# LPCB224_-_TEENSY.net
KiCad netlist of a schematic drawn in Altium Designer
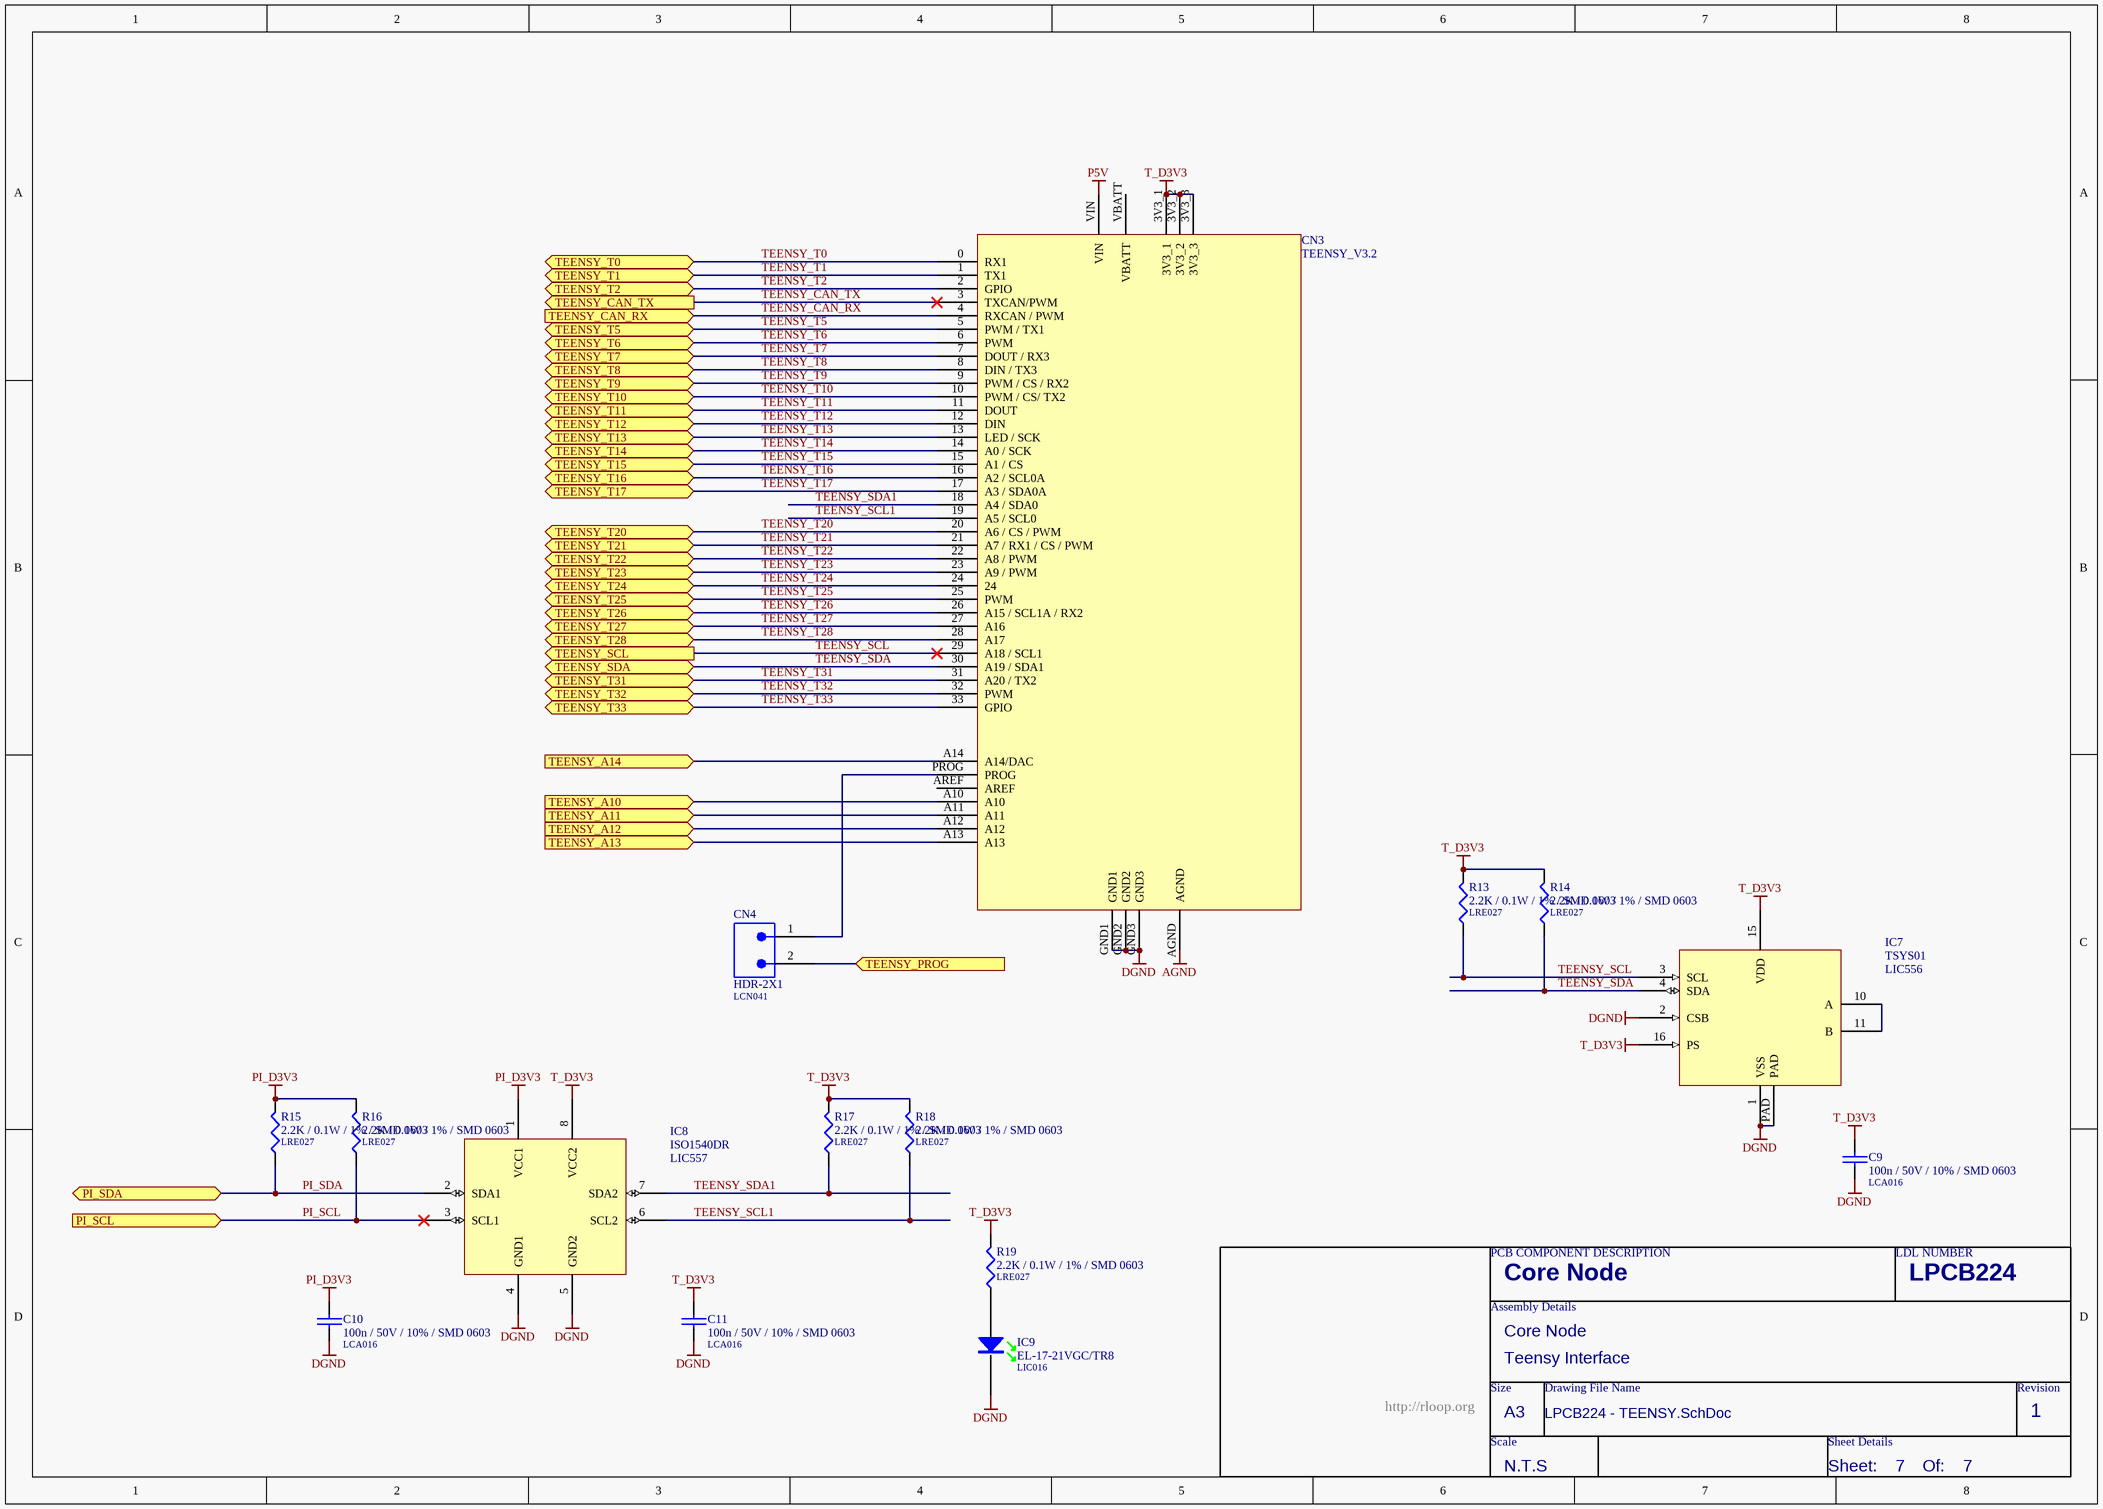
[diagram p0: LPCB224 - TEENSY.SchDoc]

(export (version "E")
  (design (tool "Eeschema 10.0.6"))
  (components
    (comp (ref "C9")
      (value "100n / 50V / 10% / SMD 0603")
      (footprint "LFP011__CC1608-0603-IPC7351_B")
      (description "Capacitor, Ceramic Chip, 100nF (0.1uF), 50V, 5%, SMD 0603 [LCA016]")
      (fields (field (name "LDL_NUMBER") "LCA016"))
      (libsource (lib "LDL_Capacitors") (part "100n / 50V / 10% / SMD 0603"))
    )
    (comp (ref "C10")
      (value "100n / 50V / 10% / SMD 0603")
      (footprint "LFP011__CC1608-0603-IPC7351_B")
      (description "Capacitor, Ceramic Chip, 100nF (0.1uF), 50V, 5%, SMD 0603 [LCA016]")
      (fields (field (name "LDL_NUMBER") "LCA016"))
      (libsource (lib "LDL_Capacitors") (part "100n / 50V / 10% / SMD 0603"))
    )
    (comp (ref "C11")
      (value "100n / 50V / 10% / SMD 0603")
      (footprint "LFP011__CC1608-0603-IPC7351_B")
      (description "Capacitor, Ceramic Chip, 100nF (0.1uF), 50V, 5%, SMD 0603 [LCA016]")
      (fields (field (name "LDL_NUMBER") "LCA016"))
      (libsource (lib "LDL_Capacitors") (part "100n / 50V / 10% / SMD 0603"))
    )
    (comp (ref "CN3")
      (value "TEENSY_V3.2")
      (footprint "TEENSY_V3.2")
      (libsource (lib "LDL_Semiconductors") (part "TEENSY_V3.2"))
    )
    (comp (ref "CN4")
      (value "HDR-2X1")
      (footprint "HDR-2X1")
      (description "Header, 2.54mm (0.1in), 2 Pins x 1 Row (40 Per Row In Strip)")
      (fields (field (name "LDL_NUMBER") "LCN041"))
      (libsource (lib "LDL_Connectors") (part "HDR-2X1"))
    )
    (comp (ref "IC7")
      (value "TSYS01")
      (footprint "LFP135__QFN65P400X400X80_HS-17M")
      (description "IC, Digital Temp Sensor, SMD QFN16 [LIC556]")
      (fields (field (name "LDL_NUMBER") "LIC556"))
      (libsource (lib "LDL_Semiconductors") (part "TSYS01"))
    )
    (comp (ref "IC8")
      (value "ISO1540DR")
      (footprint "LFP097__SOIC150-8")
      (description "IC, Digital Isolator for I2C, SMD SOIC8")
      (fields (field (name "LDL_NUMBER") "LIC557"))
      (libsource (lib "LDL_Semiconductors") (part "ISO1540DR"))
    )
    (comp (ref "IC9")
      (value "EL-17-21VGC/TR8")
      (footprint "CR2012-0805-LED")
      (description "LED, SMD, 0805 Green [LIC016]")
      (fields (field (name "LDL_NUMBER") "LIC016"))
      (libsource (lib "LDL_Semiconductors") (part "EL-17-21VGC/TR8"))
    )
    (comp (ref "R13")
      (value "2.2K / 0.1W / 1% / SMD 0603")
      (footprint "LFP020__CR1608-0603-IPC7351_B")
      (description "Resistor, Ceramic Chip, 2.2K, 0.1W, 1%, SMD 0603 [LRE027]")
      (fields (field (name "LDL_NUMBER") "LRE027"))
      (libsource (lib "LDL_Resistors") (part "2.2K / 0.1W / 1% / SMD 0603"))
    )
    (comp (ref "R14")
      (value "2.2K / 0.1W / 1% / SMD 0603")
      (footprint "LFP020__CR1608-0603-IPC7351_B")
      (description "Resistor, Ceramic Chip, 2.2K, 0.1W, 1%, SMD 0603 [LRE027]")
      (fields (field (name "LDL_NUMBER") "LRE027"))
      (libsource (lib "LDL_Resistors") (part "2.2K / 0.1W / 1% / SMD 0603"))
    )
    (comp (ref "R15")
      (value "2.2K / 0.1W / 1% / SMD 0603")
      (footprint "LFP020__CR1608-0603-IPC7351_B")
      (description "Resistor, Ceramic Chip, 2.2K, 0.1W, 1%, SMD 0603 [LRE027]")
      (fields (field (name "LDL_NUMBER") "LRE027"))
      (libsource (lib "LDL_Resistors") (part "2.2K / 0.1W / 1% / SMD 0603"))
    )
    (comp (ref "R16")
      (value "2.2K / 0.1W / 1% / SMD 0603")
      (footprint "LFP020__CR1608-0603-IPC7351_B")
      (description "Resistor, Ceramic Chip, 2.2K, 0.1W, 1%, SMD 0603 [LRE027]")
      (fields (field (name "LDL_NUMBER") "LRE027"))
      (libsource (lib "LDL_Resistors") (part "2.2K / 0.1W / 1% / SMD 0603"))
    )
    (comp (ref "R17")
      (value "2.2K / 0.1W / 1% / SMD 0603")
      (footprint "LFP020__CR1608-0603-IPC7351_B")
      (description "Resistor, Ceramic Chip, 2.2K, 0.1W, 1%, SMD 0603 [LRE027]")
      (fields (field (name "LDL_NUMBER") "LRE027"))
      (libsource (lib "LDL_Resistors") (part "2.2K / 0.1W / 1% / SMD 0603"))
    )
    (comp (ref "R18")
      (value "2.2K / 0.1W / 1% / SMD 0603")
      (footprint "LFP020__CR1608-0603-IPC7351_B")
      (description "Resistor, Ceramic Chip, 2.2K, 0.1W, 1%, SMD 0603 [LRE027]")
      (fields (field (name "LDL_NUMBER") "LRE027"))
      (libsource (lib "LDL_Resistors") (part "2.2K / 0.1W / 1% / SMD 0603"))
    )
    (comp (ref "R19")
      (value "2.2K / 0.1W / 1% / SMD 0603")
      (footprint "LFP020__CR1608-0603-IPC7351_B")
      (description "Resistor, Ceramic Chip, 2.2K, 0.1W, 1%, SMD 0603 [LRE027]")
      (fields (field (name "LDL_NUMBER") "LRE027"))
      (libsource (lib "LDL_Resistors") (part "2.2K / 0.1W / 1% / SMD 0603"))
    )
  )
  (nets
    (net (code "1") (name "/PI_SCL") (class "Default")
      (node (ref "IC8") (pin "3") (pinfunction "SCL1_3") (pintype "bidirectional"))
      (node (ref "R16") (pin "1") (pintype "passive"))
    )
    (net (code "2") (name "/PI_SDA") (class "Default")
      (node (ref "IC8") (pin "2") (pinfunction "SDA1_2") (pintype "bidirectional"))
      (node (ref "R15") (pin "1") (pintype "passive"))
    )
    (net (code "3") (name "/TEENSY_A10") (class "Default")
      (node (ref "CN3") (pin "A10") (pinfunction "A10_A10") (pintype "passive"))
    )
    (net (code "4") (name "/TEENSY_A11") (class "Default")
      (node (ref "CN3") (pin "A11") (pinfunction "A11_A11") (pintype "passive"))
    )
    (net (code "5") (name "/TEENSY_A12") (class "Default")
      (node (ref "CN3") (pin "A12") (pinfunction "A12_A12") (pintype "passive"))
    )
    (net (code "6") (name "/TEENSY_A13") (class "Default")
      (node (ref "CN3") (pin "A13") (pinfunction "A13_A13") (pintype "passive"))
    )
    (net (code "7") (name "/TEENSY_A14") (class "Default")
      (node (ref "CN3") (pin "A14") (pinfunction "A14/DAC_A14") (pintype "passive"))
    )
    (net (code "8") (name "/TEENSY_CAN_RX") (class "Default")
      (node (ref "CN3") (pin "4") (pinfunction "RXCAN_/_PWM_4") (pintype "passive"))
    )
    (net (code "9") (name "/TEENSY_CAN_TX") (class "Default")
      (node (ref "CN3") (pin "3") (pinfunction "TXCAN/PWM_3") (pintype "passive+no_connect"))
    )
    (net (code "10") (name "/TEENSY_PROG") (class "Default")
      (node (ref "CN4") (pin "2") (pinfunction "2_2") (pintype "passive"))
    )
    (net (code "11") (name "/TEENSY_SCL") (class "Default")
      (node (ref "CN3") (pin "29") (pinfunction "A18_/_SCL1_29") (pintype "passive"))
      (node (ref "IC7") (pin "3") (pinfunction "SCL_3") (pintype "input"))
      (node (ref "R13") (pin "1") (pintype "passive"))
    )
    (net (code "12") (name "/TEENSY_SCL1") (class "Default")
      (node (ref "CN3") (pin "19") (pinfunction "A5_/_SCL0_19") (pintype "passive"))
      (node (ref "IC8") (pin "6") (pinfunction "SCL2_6") (pintype "bidirectional"))
      (node (ref "R18") (pin "1") (pintype "passive"))
    )
    (net (code "13") (name "/TEENSY_SDA") (class "Default")
      (node (ref "CN3") (pin "30") (pinfunction "A19_/_SDA1_30") (pintype "passive"))
      (node (ref "IC7") (pin "4") (pinfunction "SDA_4") (pintype "bidirectional"))
      (node (ref "R14") (pin "1") (pintype "passive"))
    )
    (net (code "14") (name "/TEENSY_SDA1") (class "Default")
      (node (ref "CN3") (pin "18") (pinfunction "A4_/_SDA0_18") (pintype "passive"))
      (node (ref "IC8") (pin "7") (pinfunction "SDA2_7") (pintype "bidirectional"))
      (node (ref "R17") (pin "1") (pintype "passive"))
    )
    (net (code "15") (name "/TEENSY_T0") (class "Default")
      (node (ref "CN3") (pin "0") (pinfunction "RX1_0") (pintype "passive"))
    )
    (net (code "16") (name "/TEENSY_T1") (class "Default")
      (node (ref "CN3") (pin "1") (pinfunction "TX1_1") (pintype "passive"))
    )
    (net (code "17") (name "/TEENSY_T2") (class "Default")
      (node (ref "CN3") (pin "2") (pinfunction "GPIO_2") (pintype "passive"))
    )
    (net (code "18") (name "/TEENSY_T5") (class "Default")
      (node (ref "CN3") (pin "5") (pinfunction "PWM_/_TX1_5") (pintype "passive"))
    )
    (net (code "19") (name "/TEENSY_T6") (class "Default")
      (node (ref "CN3") (pin "6") (pinfunction "PWM_6") (pintype "passive"))
    )
    (net (code "20") (name "/TEENSY_T7") (class "Default")
      (node (ref "CN3") (pin "7") (pinfunction "DOUT_/_RX3_7") (pintype "passive"))
    )
    (net (code "21") (name "/TEENSY_T8") (class "Default")
      (node (ref "CN3") (pin "8") (pinfunction "DIN_/_TX3_8") (pintype "passive"))
    )
    (net (code "22") (name "/TEENSY_T9") (class "Default")
      (node (ref "CN3") (pin "9") (pinfunction "PWM_/_CS_/_RX2_9") (pintype "passive"))
    )
    (net (code "23") (name "/TEENSY_T10") (class "Default")
      (node (ref "CN3") (pin "10") (pinfunction "PWM_/_CS/_TX2_10") (pintype "passive"))
    )
    (net (code "24") (name "/TEENSY_T11") (class "Default")
      (node (ref "CN3") (pin "11") (pinfunction "DOUT_11") (pintype "passive"))
    )
    (net (code "25") (name "/TEENSY_T12") (class "Default")
      (node (ref "CN3") (pin "12") (pinfunction "DIN_12") (pintype "passive"))
    )
    (net (code "26") (name "/TEENSY_T13") (class "Default")
      (node (ref "CN3") (pin "13") (pinfunction "LED_/_SCK_13") (pintype "passive"))
    )
    (net (code "27") (name "/TEENSY_T14") (class "Default")
      (node (ref "CN3") (pin "14") (pinfunction "A0_/_SCK_14") (pintype "passive"))
    )
    (net (code "28") (name "/TEENSY_T15") (class "Default")
      (node (ref "CN3") (pin "15") (pinfunction "A1_/_CS_15") (pintype "passive"))
    )
    (net (code "29") (name "/TEENSY_T16") (class "Default")
      (node (ref "CN3") (pin "16") (pinfunction "A2_/_SCL0A_16") (pintype "passive"))
    )
    (net (code "30") (name "/TEENSY_T17") (class "Default")
      (node (ref "CN3") (pin "17") (pinfunction "A3_/_SDA0A_17") (pintype "passive"))
    )
    (net (code "31") (name "/TEENSY_T20") (class "Default")
      (node (ref "CN3") (pin "20") (pinfunction "A6_/_CS_/_PWM_20") (pintype "passive"))
    )
    (net (code "32") (name "/TEENSY_T21") (class "Default")
      (node (ref "CN3") (pin "21") (pinfunction "A7_/_RX1_/_CS_/_PWM_21") (pintype "passive"))
    )
    (net (code "33") (name "/TEENSY_T22") (class "Default")
      (node (ref "CN3") (pin "22") (pinfunction "A8_/_PWM_22") (pintype "passive"))
    )
    (net (code "34") (name "/TEENSY_T23") (class "Default")
      (node (ref "CN3") (pin "23") (pinfunction "A9_/_PWM_23") (pintype "passive"))
    )
    (net (code "35") (name "/TEENSY_T24") (class "Default")
      (node (ref "CN3") (pin "24") (pinfunction "24_24") (pintype "passive"))
    )
    (net (code "36") (name "/TEENSY_T25") (class "Default")
      (node (ref "CN3") (pin "25") (pinfunction "PWM_25") (pintype "passive"))
    )
    (net (code "37") (name "/TEENSY_T26") (class "Default")
      (node (ref "CN3") (pin "26") (pinfunction "A15_/_SCL1A_/_RX2_26") (pintype "passive"))
    )
    (net (code "38") (name "/TEENSY_T27") (class "Default")
      (node (ref "CN3") (pin "27") (pinfunction "A16_27") (pintype "passive"))
    )
    (net (code "39") (name "/TEENSY_T28") (class "Default")
      (node (ref "CN3") (pin "28") (pinfunction "A17_28") (pintype "passive"))
    )
    (net (code "40") (name "/TEENSY_T31") (class "Default")
      (node (ref "CN3") (pin "31") (pinfunction "A20_/_TX2_31") (pintype "passive"))
    )
    (net (code "41") (name "/TEENSY_T32") (class "Default")
      (node (ref "CN3") (pin "32") (pinfunction "PWM_32") (pintype "passive"))
    )
    (net (code "42") (name "/TEENSY_T33") (class "Default")
      (node (ref "CN3") (pin "33") (pinfunction "GPIO_33") (pintype "passive"))
    )
    (net (code "43") (name "AGND") (class "Default")
      (node (ref "CN3") (pin "AGND") (pinfunction "AGND_AGND") (pintype "power_in"))
    )
    (net (code "44") (name "DGND") (class "Default")
      (node (ref "C10") (pin "2") (pintype "passive"))
      (node (ref "C11") (pin "2") (pintype "passive"))
      (node (ref "C9") (pin "2") (pintype "passive"))
      (node (ref "CN3") (pin "GND1") (pinfunction "GND1_GND1") (pintype "power_in"))
      (node (ref "CN3") (pin "GND2") (pinfunction "GND2_GND2") (pintype "power_in"))
      (node (ref "CN3") (pin "GND3") (pinfunction "GND3_GND3") (pintype "power_in"))
      (node (ref "IC7") (pin "1") (pinfunction "VSS_1") (pintype "power_in"))
      (node (ref "IC7") (pin "2") (pinfunction "CSB_2") (pintype "input"))
      (node (ref "IC7") (pin "PAD") (pinfunction "PAD_PAD") (pintype "power_in"))
      (node (ref "IC8") (pin "4") (pinfunction "GND1_4") (pintype "power_in"))
      (node (ref "IC8") (pin "5") (pinfunction "GND2_5") (pintype "power_in"))
      (node (ref "IC9") (pin "K") (pintype "passive"))
    )
    (net (code "45") (name "Net-(CN3-PadPROG)") (class "Default")
      (node (ref "CN3") (pin "PROG") (pinfunction "PROG_PROG") (pintype "passive"))
      (node (ref "CN4") (pin "1") (pinfunction "1_1") (pintype "passive"))
    )
    (net (code "46") (name "Net-(IC7-A)") (class "Default")
      (node (ref "IC7") (pin "10") (pinfunction "A_10") (pintype "passive"))
      (node (ref "IC7") (pin "11") (pinfunction "B_11") (pintype "passive"))
    )
    (net (code "47") (name "Net-(IC9-PadA)") (class "Default")
      (node (ref "IC9") (pin "A") (pintype "passive"))
      (node (ref "R19") (pin "1") (pintype "passive"))
    )
    (net (code "48") (name "P5V") (class "Default")
      (node (ref "CN3") (pin "VIN") (pinfunction "VIN_VIN") (pintype "power_in"))
    )
    (net (code "49") (name "PI_D3V3") (class "Default")
      (node (ref "C10") (pin "1") (pintype "passive"))
      (node (ref "IC8") (pin "1") (pinfunction "VCC1_1") (pintype "power_in"))
      (node (ref "R15") (pin "2") (pintype "passive"))
      (node (ref "R16") (pin "2") (pintype "passive"))
    )
    (net (code "50") (name "T_D3V3") (class "Default")
      (node (ref "C11") (pin "1") (pintype "passive"))
      (node (ref "C9") (pin "1") (pintype "passive"))
      (node (ref "CN3") (pin "3V3_1") (pinfunction "3V3_1_3V3_1") (pintype "power_in"))
      (node (ref "CN3") (pin "3V3_2") (pinfunction "3V3_2_3V3_2") (pintype "power_in"))
      (node (ref "CN3") (pin "3V3_3") (pinfunction "3V3_3_3V3_3") (pintype "power_in"))
      (node (ref "IC7") (pin "15") (pinfunction "VDD_15") (pintype "power_in"))
      (node (ref "IC7") (pin "16") (pinfunction "PS_16") (pintype "input"))
      (node (ref "IC8") (pin "8") (pinfunction "VCC2_8") (pintype "power_in"))
      (node (ref "R13") (pin "2") (pintype "passive"))
      (node (ref "R14") (pin "2") (pintype "passive"))
      (node (ref "R17") (pin "2") (pintype "passive"))
      (node (ref "R18") (pin "2") (pintype "passive"))
      (node (ref "R19") (pin "2") (pintype "passive"))
    )
    (net (code "51") (name "unconnected-(CN3-PadAREF)") (class "Default")
      (node (ref "CN3") (pin "AREF") (pinfunction "AREF_AREF") (pintype "passive"))
    )
    (net (code "52") (name "unconnected-(CN3-PadVBATT)") (class "Default")
      (node (ref "CN3") (pin "VBATT") (pinfunction "VBATT_VBATT") (pintype "power_in"))
    )
  )
)
